# MR_Motor_Control.net
KiCad netlist of a schematic drawn in Altium Designer
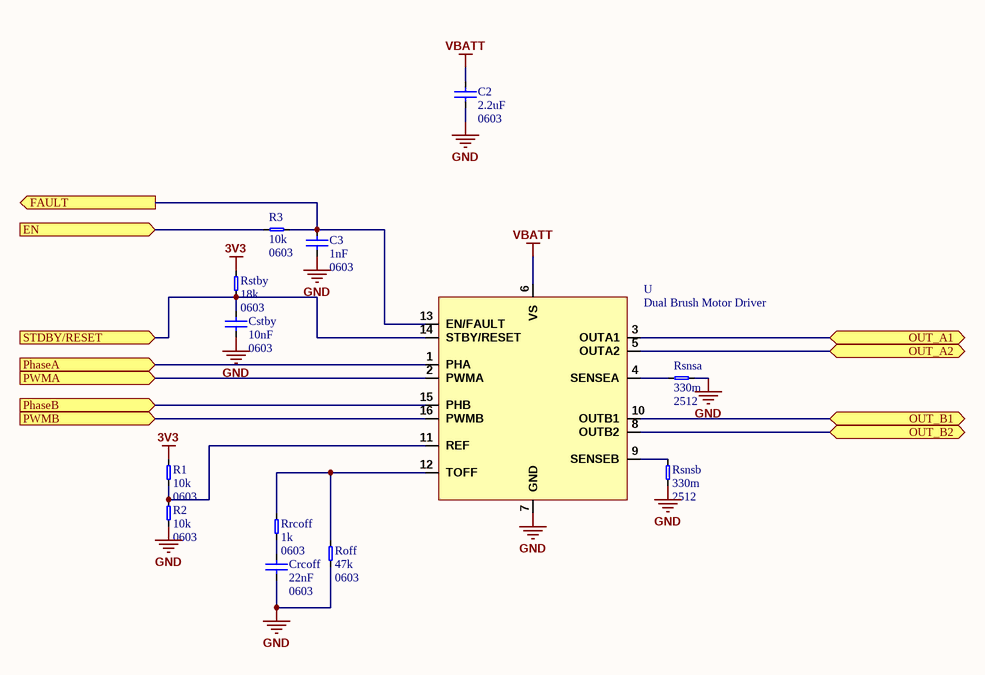
[diagram p0: MR_Motor_Control.SchDoc]

(export (version "E")
  (design (tool "Eeschema 10.0.6"))
  (components
    (comp (ref "C2")
      (value "2.2uF")
      (footprint "0603_CAP_LD")
      (description "Ceramic Capacitor")
      (fields (field (name "PACKAGE") "0603") (field (name "Comment") "CerCap"))
      (libsource (lib "MiniRobot") (part "CerCap"))
    )
    (comp (ref "C3")
      (value "1nF")
      (footprint "0603_CAP_LD")
      (description "Ceramic Capacitor")
      (fields (field (name "PACKAGE") "0603") (field (name "Comment") "CerCap"))
      (libsource (lib "MiniRobot") (part "CerCap"))
    )
    (comp (ref "Crcoff")
      (value "22nF")
      (footprint "0603_CAP_LD")
      (description "Ceramic Capacitor")
      (fields (field (name "PACKAGE") "0603") (field (name "Comment") "CerCap"))
      (libsource (lib "MiniRobot") (part "CerCap"))
    )
    (comp (ref "Cstby")
      (value "10nF")
      (footprint "0603_CAP_LD")
      (description "Ceramic Capacitor")
      (fields (field (name "PACKAGE") "0603") (field (name "Comment") "CerCap"))
      (libsource (lib "MiniRobot") (part "CerCap"))
    )
    (comp (ref "R1")
      (value "10k")
      (footprint "0603_RES_LD")
      (description "Resistor")
      (fields (field (name "PACKAGE") "0603"))
      (libsource (lib "MiniRobot") (part "Resistor"))
    )
    (comp (ref "R2")
      (value "10k")
      (footprint "0603_RES_LD")
      (description "Resistor")
      (fields (field (name "PACKAGE") "0603"))
      (libsource (lib "MiniRobot") (part "Resistor"))
    )
    (comp (ref "R3")
      (value "10k")
      (footprint "0603_RES_LD")
      (description "Resistor")
      (fields (field (name "PACKAGE") "0603"))
      (libsource (lib "MiniRobot") (part "Resistor"))
    )
    (comp (ref "Roff")
      (value "47k")
      (footprint "0603_RES_LD")
      (description "Resistor")
      (fields (field (name "PACKAGE") "0603"))
      (libsource (lib "MiniRobot") (part "Resistor"))
    )
    (comp (ref "Rrcoff")
      (value "1k")
      (footprint "0603_RES_LD")
      (description "Resistor")
      (fields (field (name "PACKAGE") "0603"))
      (libsource (lib "MiniRobot") (part "Resistor"))
    )
    (comp (ref "Rsnsa")
      (value "330m")
      (footprint "2512_RES_LD")
      (description "Resistor")
      (fields (field (name "PACKAGE") "2512"))
      (libsource (lib "MiniRobot") (part "Resistor"))
    )
    (comp (ref "Rsnsb")
      (value "330m")
      (footprint "2512_RES_LD")
      (description "Resistor")
      (fields (field (name "PACKAGE") "2512"))
      (libsource (lib "MiniRobot") (part "Resistor"))
    )
    (comp (ref "Rstby")
      (value "18k")
      (footprint "0603_RES_LD")
      (description "Resistor")
      (fields (field (name "PACKAGE") "0603"))
      (libsource (lib "MiniRobot") (part "Resistor"))
    )
    (comp (ref "U")
      (value "Dual Brush Motor Driver")
      (footprint "QFN-STSPIN240")
      (description "ST Dual Motor Driver")
      (libsource (lib "MiniRobot") (part "STSPIN240"))
    )
  )
  (nets
    (net (code "1") (name "/EN") (class "Default")
      (node (ref "R3") (pin "1") (pinfunction "1_1") (pintype "passive"))
    )
    (net (code "2") (name "/FAULT") (class "Default")
      (node (ref "C3") (pin "2") (pinfunction "2_2") (pintype "passive"))
      (node (ref "R3") (pin "2") (pinfunction "2_2") (pintype "passive"))
      (node (ref "U") (pin "13") (pinfunction "EN/FAULT_13") (pintype "passive"))
    )
    (net (code "3") (name "/OUT_A1") (class "Default")
      (node (ref "U") (pin "3") (pinfunction "OUTA1_3") (pintype "passive"))
    )
    (net (code "4") (name "/OUT_A2") (class "Default")
      (node (ref "U") (pin "5") (pinfunction "OUTA2_5") (pintype "passive"))
    )
    (net (code "5") (name "/OUT_B1") (class "Default")
      (node (ref "U") (pin "10") (pinfunction "OUTB1_10") (pintype "passive"))
    )
    (net (code "6") (name "/OUT_B2") (class "Default")
      (node (ref "U") (pin "8") (pinfunction "OUTB2_8") (pintype "passive"))
    )
    (net (code "7") (name "/PWMA") (class "Default")
      (node (ref "U") (pin "2") (pinfunction "PWMA_2") (pintype "passive"))
    )
    (net (code "8") (name "/PWMB") (class "Default")
      (node (ref "U") (pin "16") (pinfunction "PWMB_16") (pintype "passive"))
    )
    (net (code "9") (name "/PhaseA") (class "Default")
      (node (ref "U") (pin "1") (pinfunction "PHA_1") (pintype "passive"))
    )
    (net (code "10") (name "/PhaseB") (class "Default")
      (node (ref "U") (pin "15") (pinfunction "PHB_15") (pintype "passive"))
    )
    (net (code "11") (name "/STDBY{slash}RESET") (class "Default")
      (node (ref "Cstby") (pin "2") (pinfunction "2_2") (pintype "passive"))
      (node (ref "Rstby") (pin "1") (pinfunction "1_1") (pintype "passive"))
      (node (ref "U") (pin "14") (pinfunction "STBY/RESET_14") (pintype "passive"))
    )
    (net (code "12") (name "3V3") (class "Default")
      (node (ref "R1") (pin "2") (pinfunction "2_2") (pintype "passive"))
      (node (ref "Rstby") (pin "2") (pinfunction "2_2") (pintype "passive"))
    )
    (net (code "13") (name "GND") (class "Default")
      (node (ref "C2") (pin "1") (pinfunction "1_1") (pintype "passive"))
      (node (ref "C3") (pin "1") (pinfunction "1_1") (pintype "passive"))
      (node (ref "Crcoff") (pin "1") (pinfunction "1_1") (pintype "passive"))
      (node (ref "Cstby") (pin "1") (pinfunction "1_1") (pintype "passive"))
      (node (ref "R2") (pin "1") (pinfunction "1_1") (pintype "passive"))
      (node (ref "Roff") (pin "1") (pinfunction "1_1") (pintype "passive"))
      (node (ref "Rsnsa") (pin "1") (pinfunction "1_1") (pintype "passive"))
      (node (ref "Rsnsb") (pin "1") (pinfunction "1_1") (pintype "passive"))
      (node (ref "U") (pin "7") (pinfunction "GND_7") (pintype "passive"))
    )
    (net (code "14") (name "Net-(Crcoff-Pad2)") (class "Default")
      (node (ref "Crcoff") (pin "2") (pinfunction "2_2") (pintype "passive"))
      (node (ref "Rrcoff") (pin "1") (pinfunction "1_1") (pintype "passive"))
    )
    (net (code "15") (name "Net-(U-REF)") (class "Default")
      (node (ref "R1") (pin "1") (pinfunction "1_1") (pintype "passive"))
      (node (ref "R2") (pin "2") (pinfunction "2_2") (pintype "passive"))
      (node (ref "U") (pin "11") (pinfunction "REF_11") (pintype "passive"))
    )
    (net (code "16") (name "Net-(U-SENSEA)") (class "Default")
      (node (ref "Rsnsa") (pin "2") (pinfunction "2_2") (pintype "passive"))
      (node (ref "U") (pin "4") (pinfunction "SENSEA_4") (pintype "passive"))
    )
    (net (code "17") (name "Net-(U-SENSEB)") (class "Default")
      (node (ref "Rsnsb") (pin "2") (pinfunction "2_2") (pintype "passive"))
      (node (ref "U") (pin "9") (pinfunction "SENSEB_9") (pintype "passive"))
    )
    (net (code "18") (name "Net-(U-TOFF)") (class "Default")
      (node (ref "Roff") (pin "2") (pinfunction "2_2") (pintype "passive"))
      (node (ref "Rrcoff") (pin "2") (pinfunction "2_2") (pintype "passive"))
      (node (ref "U") (pin "12") (pinfunction "TOFF_12") (pintype "passive"))
    )
    (net (code "19") (name "VBATT") (class "Default")
      (node (ref "C2") (pin "2") (pinfunction "2_2") (pintype "passive"))
      (node (ref "U") (pin "6") (pinfunction "VS_6") (pintype "passive"))
    )
  )
)
